# Inputs.net
KiCad netlist of a schematic drawn in Altium Designer
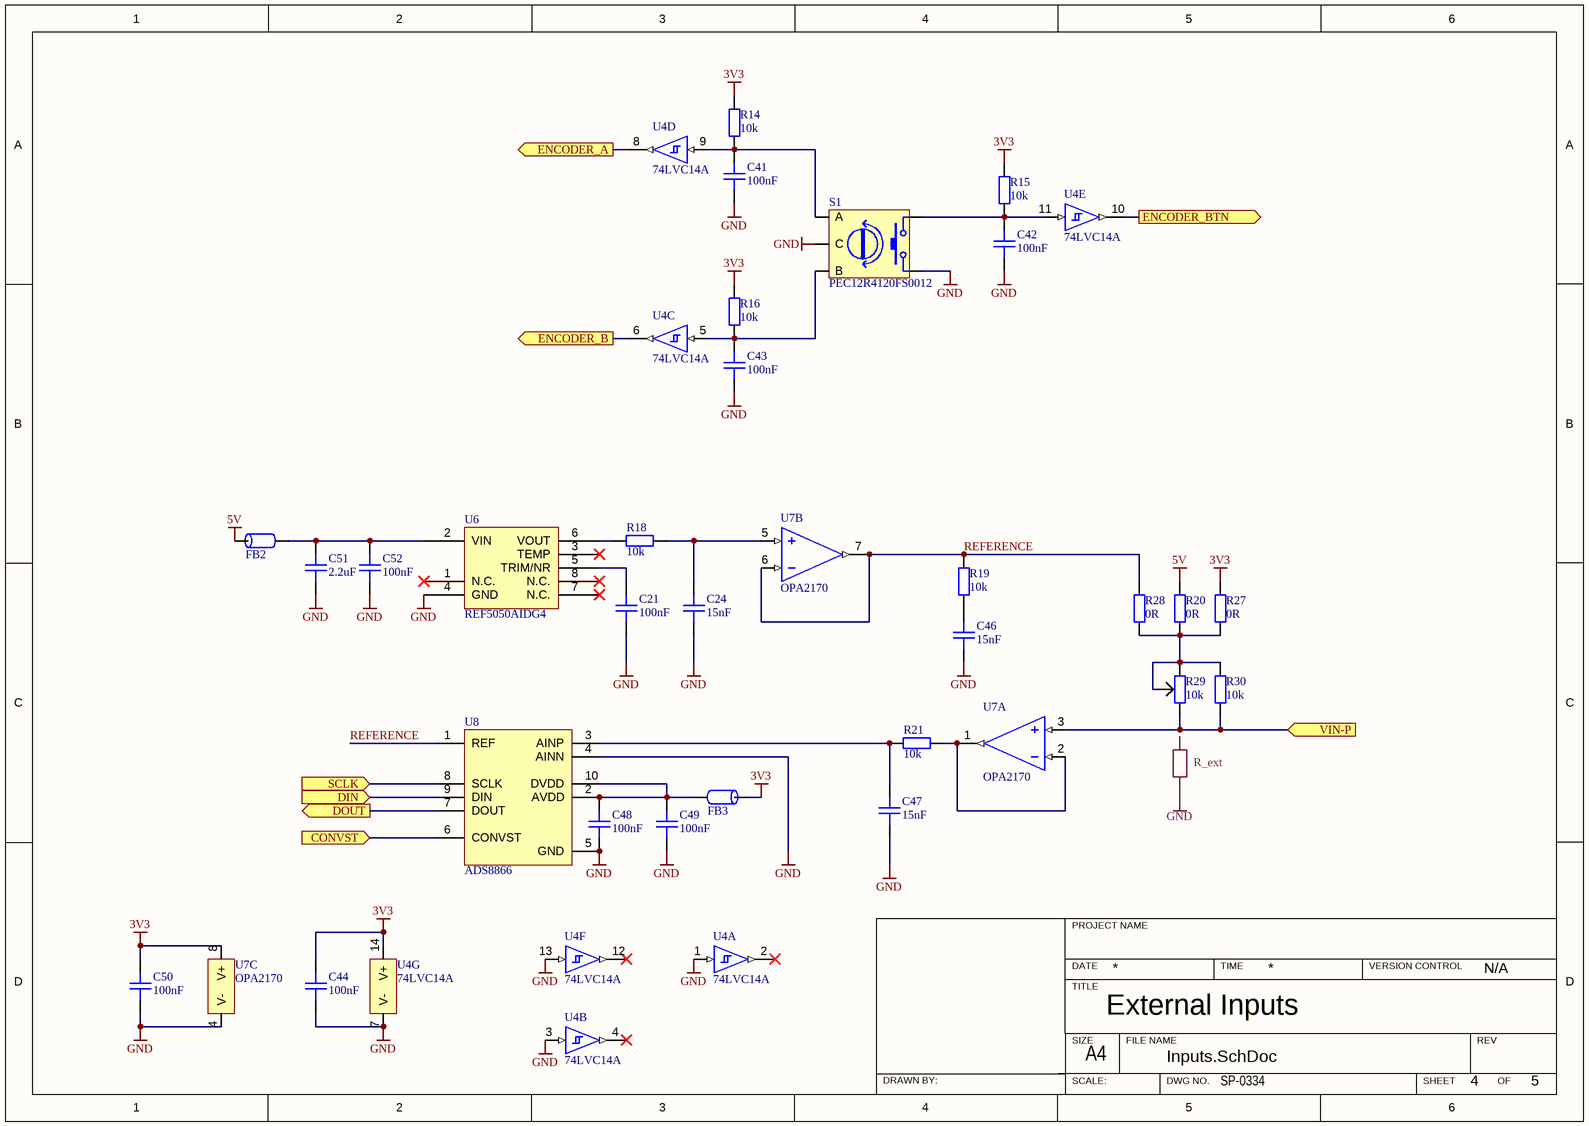
[diagram p0: Inputs.SchDoc]

(export (version "E")
  (design (tool "Eeschema 10.0.6"))
  (components
    (comp (ref "C21")
      (value "100nF")
      (footprint "CAP-0603")
      (description "Capacitor Non-Polar")
      (libsource (lib "MasterLib") (part "CAP - 0603"))
    )
    (comp (ref "C24")
      (value "15nF")
      (footprint "CAP-0603")
      (description "Capacitor Non-Polar")
      (libsource (lib "MasterLib") (part "CAP - 0603"))
    )
    (comp (ref "C41")
      (value "100nF")
      (footprint "CAP-0603")
      (description "Capacitor Non-Polar")
      (libsource (lib "MasterLib") (part "CAP - 0603"))
    )
    (comp (ref "C42")
      (value "100nF")
      (footprint "CAP-0603")
      (description "Capacitor Non-Polar")
      (libsource (lib "MasterLib") (part "CAP - 0603"))
    )
    (comp (ref "C43")
      (value "100nF")
      (footprint "CAP-0603")
      (description "Capacitor Non-Polar")
      (libsource (lib "MasterLib") (part "CAP - 0603"))
    )
    (comp (ref "C44")
      (value "100nF")
      (footprint "CAP-0603")
      (description "Capacitor Non-Polar")
      (libsource (lib "MasterLib") (part "CAP - 0603"))
    )
    (comp (ref "C46")
      (value "15nF")
      (footprint "CAP-0603")
      (description "Capacitor Non-Polar")
      (libsource (lib "MasterLib") (part "CAP - 0603"))
    )
    (comp (ref "C47")
      (value "15nF")
      (footprint "CAP-0603")
      (description "Capacitor Non-Polar")
      (libsource (lib "MasterLib") (part "CAP - 0603"))
    )
    (comp (ref "C48")
      (value "100nF")
      (footprint "CAP-0603")
      (description "Capacitor Non-Polar")
      (libsource (lib "MasterLib") (part "CAP - 0603"))
    )
    (comp (ref "C49")
      (value "100nF")
      (footprint "CAP-0603")
      (description "Capacitor Non-Polar")
      (libsource (lib "MasterLib") (part "CAP - 0603"))
    )
    (comp (ref "C50")
      (value "100nF")
      (footprint "CAP-0603")
      (description "Capacitor Non-Polar")
      (libsource (lib "MasterLib") (part "CAP - 0603"))
    )
    (comp (ref "C51")
      (value "2.2uF")
      (footprint "CAP-0805")
      (description "Capacitor Non-Polar")
      (libsource (lib "MasterLib") (part "CAP - 0805"))
    )
    (comp (ref "C52")
      (value "100nF")
      (footprint "CAP-0603")
      (description "Capacitor Non-Polar")
      (libsource (lib "MasterLib") (part "CAP - 0603"))
    )
    (comp (ref "FB2")
      (value "FB - 0603")
      (footprint "FB-0603")
      (description "Ferrit bead 0603")
      (libsource (lib "MasterLib") (part "FB - 0603"))
    )
    (comp (ref "FB3")
      (value "FB - 0603")
      (footprint "FB-0603")
      (description "Ferrit bead 0603")
      (libsource (lib "") (part "FB - 0603_1"))
    )
    (comp (ref "R14")
      (value "10k")
      (footprint "RES-0603")
      (description "Resistor")
      (libsource (lib "") (part "RES - 0603_3"))
    )
    (comp (ref "R15")
      (value "10k")
      (footprint "RES-0603")
      (description "Resistor")
      (libsource (lib "") (part "RES - 0603_1"))
    )
    (comp (ref "R16")
      (value "10k")
      (footprint "RES-0603")
      (description "Resistor")
      (libsource (lib "") (part "RES - 0603_3"))
    )
    (comp (ref "R18")
      (value "10k")
      (footprint "RES-0603")
      (description "Resistor")
      (libsource (lib "") (part "RES - 0603_2"))
    )
    (comp (ref "R19")
      (value "10k")
      (footprint "RES-0603")
      (description "Resistor")
      (libsource (lib "MasterLib") (part "RES - 0603"))
    )
    (comp (ref "R20")
      (value "0R")
      (footprint "RES-0603")
      (description "Resistor")
      (libsource (lib "MasterLib") (part "RES - 0603"))
    )
    (comp (ref "R21")
      (value "10k")
      (footprint "RES-0603")
      (description "Resistor")
      (libsource (lib "") (part "RES - 0603_2"))
    )
    (comp (ref "R27")
      (value "0R")
      (footprint "RES-0603")
      (description "Resistor")
      (libsource (lib "MasterLib") (part "RES - 0603"))
    )
    (comp (ref "R28")
      (value "0R")
      (footprint "RES-0603")
      (description "Resistor")
      (libsource (lib "MasterLib") (part "RES - 0603"))
    )
    (comp (ref "R29")
      (value "10k")
      (footprint "RES-TRIM-SMD")
      (description "Trim Potentiometer")
      (libsource (lib "MasterLib") (part "RES - POT - TRIM - SMD"))
    )
    (comp (ref "R30")
      (value "10k")
      (footprint "RES-0603")
      (description "Resistor")
      (libsource (lib "MasterLib") (part "RES - 0603"))
    )
    (comp (ref "S1")
      (value "PEC12R4120FS0012")
      (footprint "BTN-ENCODER-12pos")
      (description "Encoder with Push Button")
      (libsource (lib "MasterLib") (part "BTN - Encoder 12pos"))
    )
    (comp (ref "U4")
      (value "74LVC14A")
      (footprint "IC-SOIC-14")
      (description "6xINVERTING GATE SCHMITT-TRIGGER SO-14")
      (libsource (lib "MasterLib") (part "IC - 74LVC14"))
    )
    (comp (ref "U6")
      (value "REF5050AIDG4")
      (footprint "IC-SOIC-8")
      (description "Enhanced Product Low-Noise, Very Low Drift, Precision Voltage Reference, 5V")
      (libsource (lib "MasterLib") (part "IC - REF5050"))
    )
    (comp (ref "U7")
      (value "OPA2170")
      (footprint "IC-SOIC-8")
      (description "Low-Power, Dual-Operational Amplifiers")
      (libsource (lib "") (part "IC - OPA2170_2"))
    )
    (comp (ref "U8")
      (value "ADS8866")
      (footprint "IC-VSSOP-10")
      (description "ADC")
      (libsource (lib "MasterLib") (part "IC - ADS8866"))
    )
  )
  (nets
    (net (code "1") (name "/CONVST") (class "Default")
      (node (ref "U8") (pin "6") (pinfunction "CONVST_6") (pintype "passive"))
    )
    (net (code "2") (name "/DIN") (class "Default")
      (node (ref "U8") (pin "9") (pinfunction "DIN_9") (pintype "passive"))
    )
    (net (code "3") (name "/DOUT") (class "Default")
      (node (ref "U8") (pin "7") (pinfunction "DOUT_7") (pintype "passive"))
    )
    (net (code "4") (name "/ENCODER_A") (class "Default")
      (node (ref "U4") (pin "8") (pinfunction "Y_8") (pintype "output"))
    )
    (net (code "5") (name "/ENCODER_B") (class "Default")
      (node (ref "U4") (pin "6") (pinfunction "Y_6") (pintype "output"))
    )
    (net (code "6") (name "/ENCODER_BTN") (class "Default")
      (node (ref "U4") (pin "10") (pinfunction "Y_10") (pintype "output"))
    )
    (net (code "7") (name "/REFERENCE") (class "Default")
      (node (ref "R19") (pin "2") (pinfunction "2_2") (pintype "passive"))
      (node (ref "R28") (pin "2") (pinfunction "2_2") (pintype "passive"))
      (node (ref "U7") (pin "6") (pinfunction "IN-_6") (pintype "input"))
      (node (ref "U7") (pin "7") (pinfunction "OUT_7") (pintype "output"))
      (node (ref "U8") (pin "1") (pinfunction "REF_1") (pintype "passive"))
    )
    (net (code "8") (name "/SCLK") (class "Default")
      (node (ref "U8") (pin "8") (pinfunction "SCLK_8") (pintype "passive"))
    )
    (net (code "9") (name "/VIN-P") (class "Default")
      (node (ref "R29") (pin "3") (pinfunction "3_3") (pintype "passive"))
      (node (ref "R30") (pin "1") (pinfunction "1_1") (pintype "passive"))
      (node (ref "U7") (pin "3") (pinfunction "IN+_3") (pintype "input"))
    )
    (net (code "10") (name "3V3") (class "Default")
      (node (ref "C44") (pin "2") (pinfunction "2_2") (pintype "passive"))
      (node (ref "C50") (pin "2") (pinfunction "2_2") (pintype "passive"))
      (node (ref "FB3") (pin "1") (pinfunction "1_1") (pintype "passive"))
      (node (ref "R14") (pin "1") (pinfunction "1_1") (pintype "passive"))
      (node (ref "R15") (pin "1") (pinfunction "1_1") (pintype "passive"))
      (node (ref "R16") (pin "1") (pinfunction "1_1") (pintype "passive"))
      (node (ref "R27") (pin "2") (pinfunction "2_2") (pintype "passive"))
      (node (ref "U4") (pin "14") (pinfunction "V+_14") (pintype "power_in"))
      (node (ref "U7") (pin "8") (pinfunction "V+_8") (pintype "power_in"))
    )
    (net (code "11") (name "5V") (class "Default")
      (node (ref "FB2") (pin "1") (pinfunction "1_1") (pintype "passive"))
      (node (ref "R20") (pin "2") (pinfunction "2_2") (pintype "passive"))
    )
    (net (code "12") (name "GND") (class "Default")
      (node (ref "C21") (pin "1") (pinfunction "1_1") (pintype "passive"))
      (node (ref "C24") (pin "1") (pinfunction "1_1") (pintype "passive"))
      (node (ref "C41") (pin "1") (pinfunction "1_1") (pintype "passive"))
      (node (ref "C42") (pin "1") (pinfunction "1_1") (pintype "passive"))
      (node (ref "C43") (pin "1") (pinfunction "1_1") (pintype "passive"))
      (node (ref "C44") (pin "1") (pinfunction "1_1") (pintype "passive"))
      (node (ref "C46") (pin "1") (pinfunction "1_1") (pintype "passive"))
      (node (ref "C47") (pin "1") (pinfunction "1_1") (pintype "passive"))
      (node (ref "C48") (pin "1") (pinfunction "1_1") (pintype "passive"))
      (node (ref "C49") (pin "1") (pinfunction "1_1") (pintype "passive"))
      (node (ref "C50") (pin "1") (pinfunction "1_1") (pintype "passive"))
      (node (ref "C51") (pin "1") (pinfunction "1_1") (pintype "passive"))
      (node (ref "C52") (pin "1") (pinfunction "1_1") (pintype "passive"))
      (node (ref "S1") (pin "2") (pinfunction "C_2") (pintype "passive"))
      (node (ref "S1") (pin "5") (pinfunction "5_5") (pintype "passive"))
      (node (ref "U4") (pin "1") (pinfunction "A_1") (pintype "input"))
      (node (ref "U4") (pin "13") (pinfunction "A_13") (pintype "input"))
      (node (ref "U4") (pin "3") (pinfunction "A_3") (pintype "input"))
      (node (ref "U4") (pin "7") (pinfunction "V-_7") (pintype "power_in"))
      (node (ref "U6") (pin "4") (pinfunction "GND_4") (pintype "passive"))
      (node (ref "U7") (pin "4") (pinfunction "V-_4") (pintype "power_in"))
      (node (ref "U8") (pin "4") (pinfunction "AINN_4") (pintype "passive"))
      (node (ref "U8") (pin "5") (pinfunction "GND_5") (pintype "passive"))
    )
    (net (code "13") (name "Net-(C46-Pad2)") (class "Default")
      (node (ref "C46") (pin "2") (pinfunction "2_2") (pintype "passive"))
      (node (ref "R19") (pin "1") (pinfunction "1_1") (pintype "passive"))
    )
    (net (code "14") (name "Net-(R20-Pad1)") (class "Default")
      (node (ref "R20") (pin "1") (pinfunction "1_1") (pintype "passive"))
      (node (ref "R27") (pin "1") (pinfunction "1_1") (pintype "passive"))
      (node (ref "R28") (pin "1") (pinfunction "1_1") (pintype "passive"))
      (node (ref "R29") (pin "1") (pinfunction "1_1") (pintype "passive"))
      (node (ref "R29") (pin "2") (pinfunction "2_2") (pintype "passive"))
      (node (ref "R30") (pin "2") (pinfunction "2_2") (pintype "passive"))
    )
    (net (code "15") (name "Net-(S1-A)") (class "Default")
      (node (ref "C41") (pin "2") (pinfunction "2_2") (pintype "passive"))
      (node (ref "R14") (pin "2") (pinfunction "2_2") (pintype "passive"))
      (node (ref "S1") (pin "1") (pinfunction "A_1") (pintype "passive"))
      (node (ref "U4") (pin "9") (pinfunction "A_9") (pintype "input"))
    )
    (net (code "16") (name "Net-(S1-B)") (class "Default")
      (node (ref "C43") (pin "2") (pinfunction "2_2") (pintype "passive"))
      (node (ref "R16") (pin "2") (pinfunction "2_2") (pintype "passive"))
      (node (ref "S1") (pin "3") (pinfunction "B_3") (pintype "passive"))
      (node (ref "U4") (pin "5") (pinfunction "A_5") (pintype "input"))
    )
    (net (code "17") (name "Net-(U4E-A)") (class "Default")
      (node (ref "C42") (pin "2") (pinfunction "2_2") (pintype "passive"))
      (node (ref "R15") (pin "2") (pinfunction "2_2") (pintype "passive"))
      (node (ref "S1") (pin "4") (pinfunction "4_4") (pintype "passive"))
      (node (ref "U4") (pin "11") (pinfunction "A_11") (pintype "input"))
    )
    (net (code "18") (name "Net-(U6-TRIM{slash}NR)") (class "Default")
      (node (ref "C21") (pin "2") (pinfunction "2_2") (pintype "passive"))
      (node (ref "U6") (pin "5") (pinfunction "TRIM/NR_5") (pintype "passive"))
    )
    (net (code "19") (name "Net-(U6-VIN)") (class "Default")
      (node (ref "C51") (pin "2") (pinfunction "2_2") (pintype "passive"))
      (node (ref "C52") (pin "2") (pinfunction "2_2") (pintype "passive"))
      (node (ref "FB2") (pin "2") (pinfunction "2_2") (pintype "passive"))
      (node (ref "U6") (pin "2") (pinfunction "VIN_2") (pintype "passive"))
    )
    (net (code "20") (name "Net-(U6-VOUT)") (class "Default")
      (node (ref "R18") (pin "1") (pinfunction "1_1") (pintype "passive"))
      (node (ref "U6") (pin "6") (pinfunction "VOUT_6") (pintype "passive"))
    )
    (net (code "21") (name "Net-(U7A-IN-)") (class "Default")
      (node (ref "R21") (pin "2") (pinfunction "2_2") (pintype "passive"))
      (node (ref "U7") (pin "1") (pinfunction "OUT_1") (pintype "output"))
      (node (ref "U7") (pin "2") (pinfunction "IN-_2") (pintype "input"))
    )
    (net (code "22") (name "Net-(U7B-IN+)") (class "Default")
      (node (ref "C24") (pin "2") (pinfunction "2_2") (pintype "passive"))
      (node (ref "R18") (pin "2") (pinfunction "2_2") (pintype "passive"))
      (node (ref "U7") (pin "5") (pinfunction "IN+_5") (pintype "input"))
    )
    (net (code "23") (name "Net-(U8-AINP)") (class "Default")
      (node (ref "C47") (pin "2") (pinfunction "2_2") (pintype "passive"))
      (node (ref "R21") (pin "1") (pinfunction "1_1") (pintype "passive"))
      (node (ref "U8") (pin "3") (pinfunction "AINP_3") (pintype "passive"))
    )
    (net (code "24") (name "Net-(U8-AVDD)") (class "Default")
      (node (ref "C48") (pin "2") (pinfunction "2_2") (pintype "passive"))
      (node (ref "C49") (pin "2") (pinfunction "2_2") (pintype "passive"))
      (node (ref "FB3") (pin "2") (pinfunction "2_2") (pintype "passive"))
      (node (ref "U8") (pin "10") (pinfunction "DVDD_10") (pintype "passive"))
      (node (ref "U8") (pin "2") (pinfunction "AVDD_2") (pintype "passive"))
    )
    (net (code "25") (name "unconnected-(U4A-Y-Pad2)") (class "Default")
      (node (ref "U4") (pin "2") (pinfunction "Y_2") (pintype "output+no_connect"))
    )
    (net (code "26") (name "unconnected-(U4B-Y-Pad4)") (class "Default")
      (node (ref "U4") (pin "4") (pinfunction "Y_4") (pintype "output+no_connect"))
    )
    (net (code "27") (name "unconnected-(U4F-Y-Pad12)") (class "Default")
      (node (ref "U4") (pin "12") (pinfunction "Y_12") (pintype "output+no_connect"))
    )
    (net (code "28") (name "unconnected-(U6-N.C.-Pad1)") (class "Default")
      (node (ref "U6") (pin "1") (pinfunction "N.C._1") (pintype "passive+no_connect"))
    )
    (net (code "29") (name "unconnected-(U6-N.C.-Pad7)") (class "Default")
      (node (ref "U6") (pin "7") (pinfunction "N.C._7") (pintype "passive+no_connect"))
    )
    (net (code "30") (name "unconnected-(U6-N.C.-Pad8)") (class "Default")
      (node (ref "U6") (pin "8") (pinfunction "N.C._8") (pintype "passive+no_connect"))
    )
    (net (code "31") (name "unconnected-(U6-TEMP-Pad3)") (class "Default")
      (node (ref "U6") (pin "3") (pinfunction "TEMP_3") (pintype "passive+no_connect"))
    )
  )
)
